# led30Sheet1.net
KiCad netlist of a schematic drawn in Altium Designer
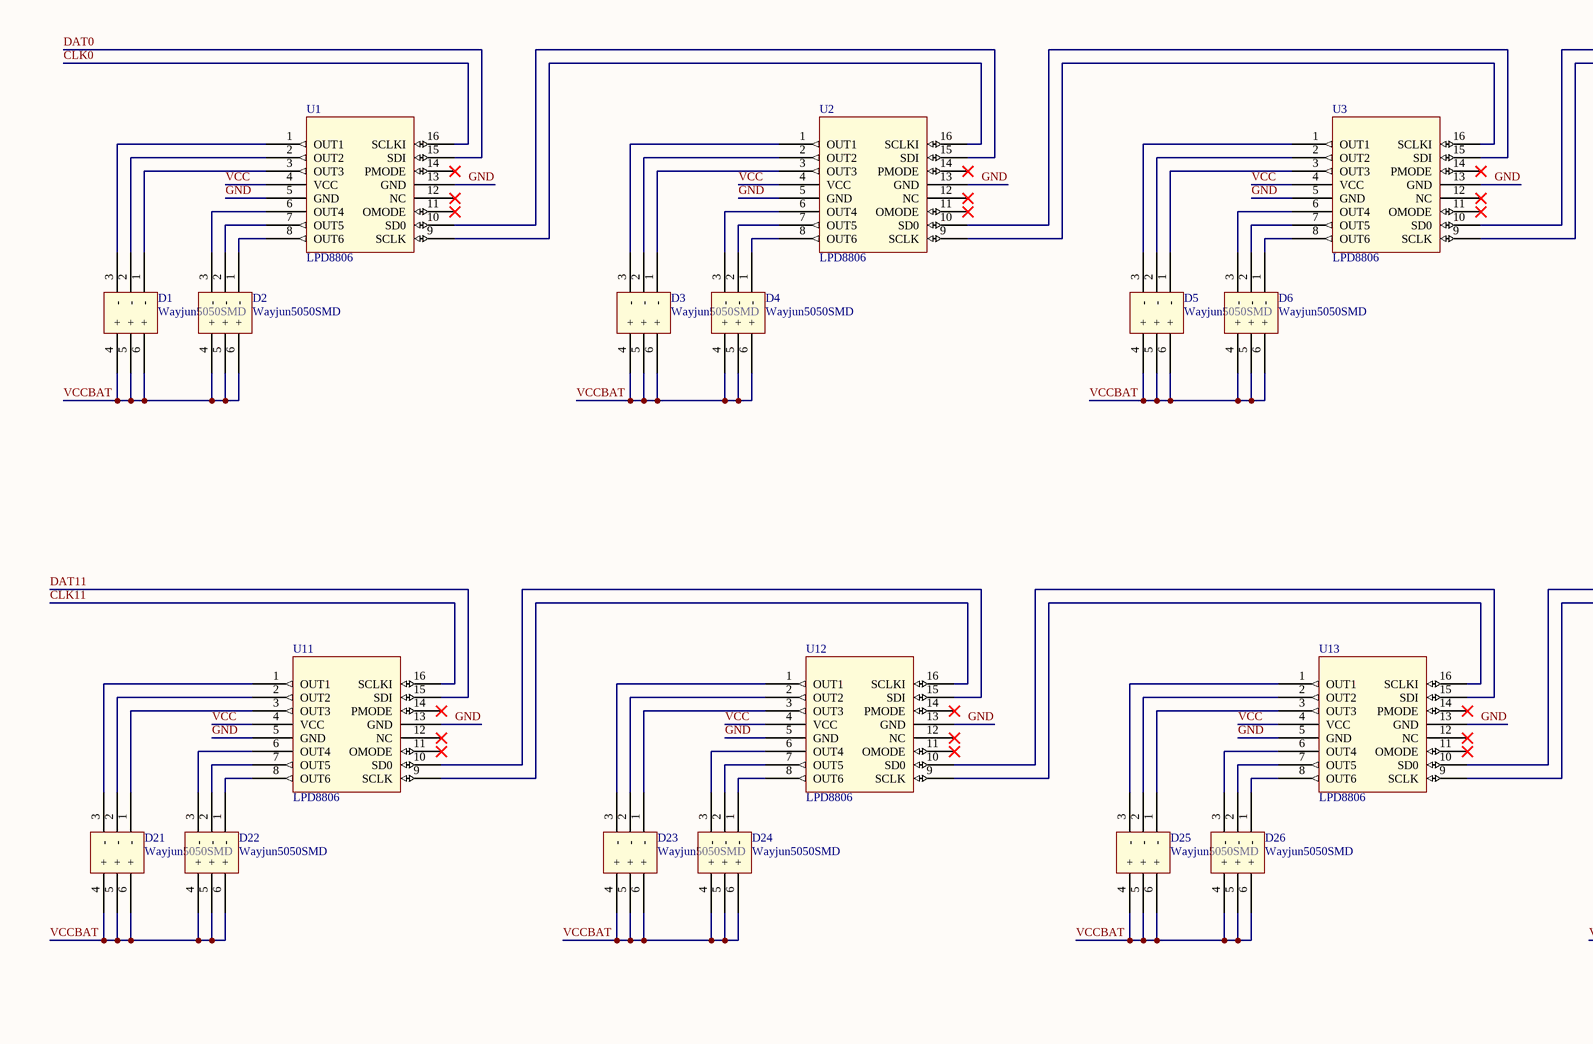
[diagram p0: led30Sheet1.SchDoc, top left]
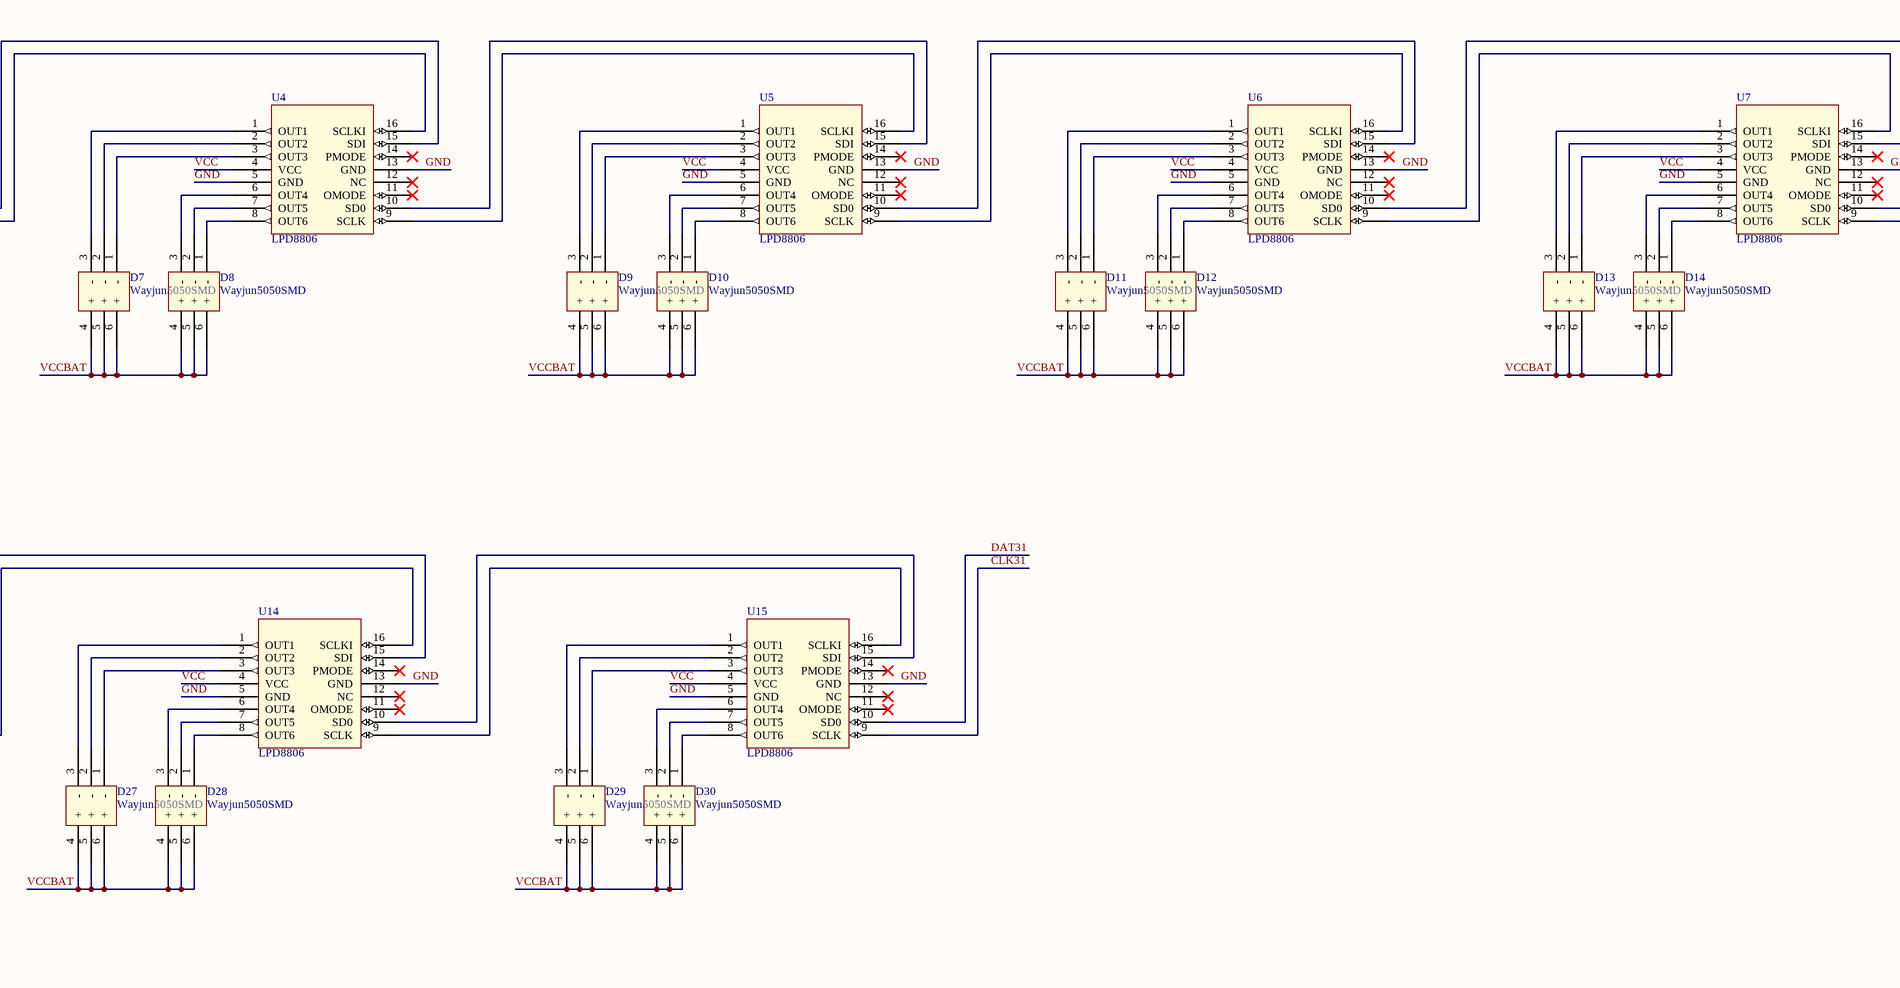
[diagram p1: led30Sheet1.SchDoc, top middle]
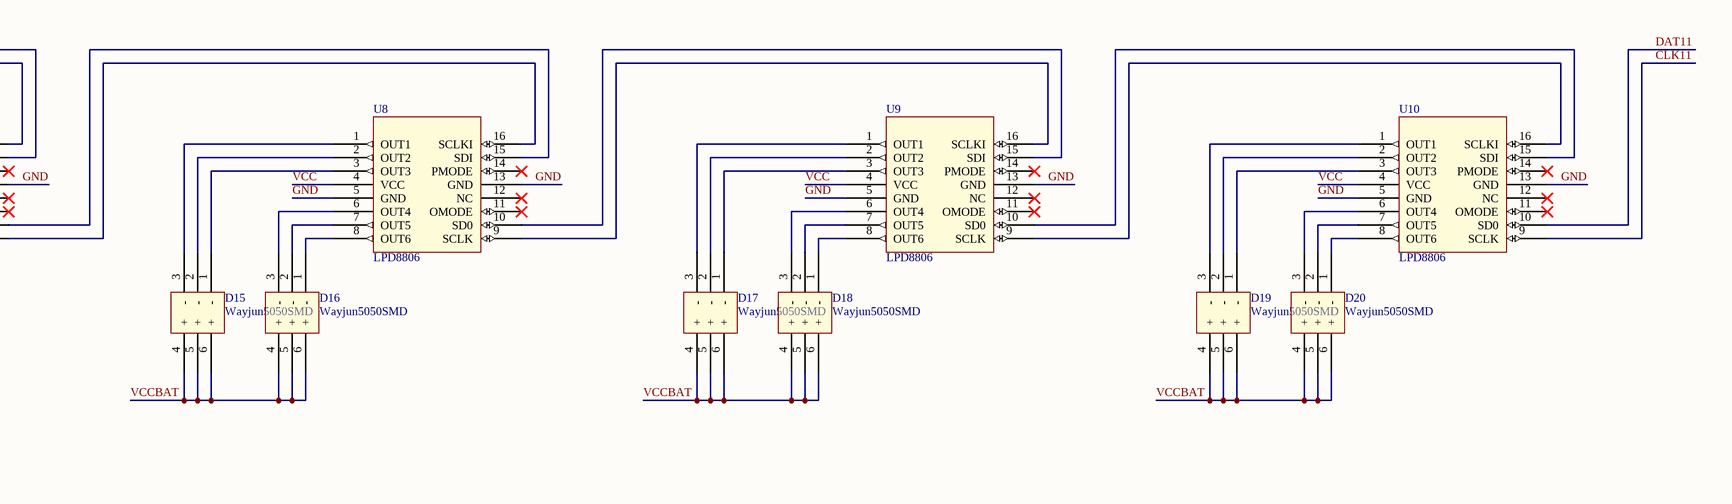
[diagram p2: led30Sheet1.SchDoc, top right]
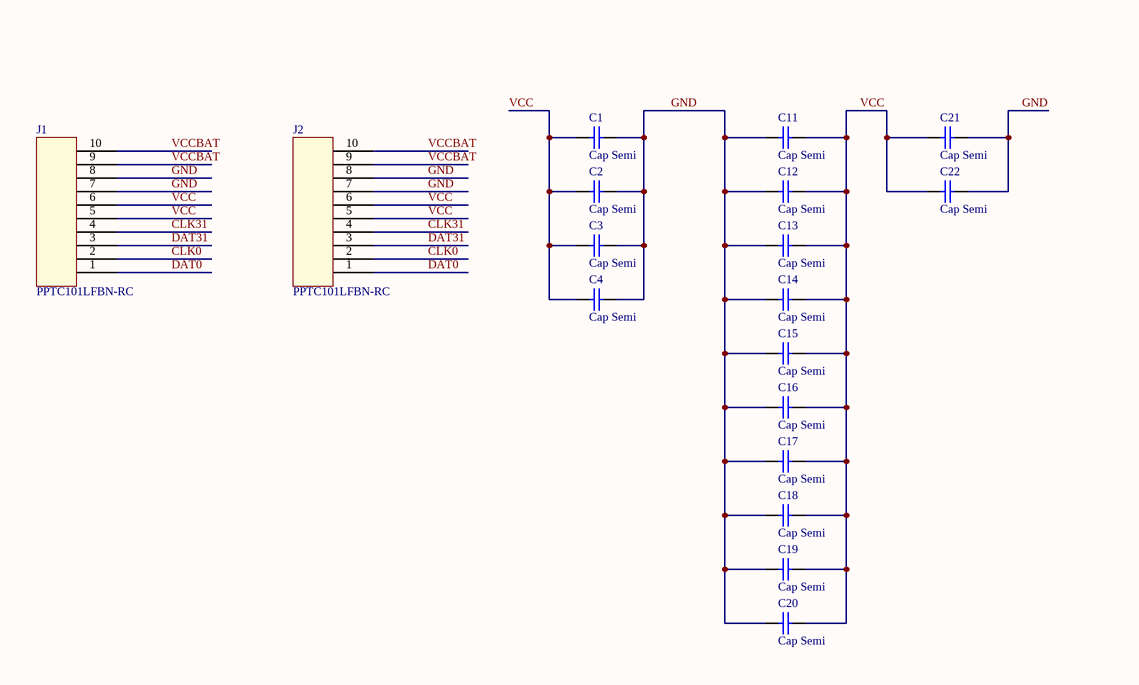
[diagram p3: led30Sheet1.SchDoc, bottom left]

(export (version "E")
  (design (tool "Eeschema 10.0.6"))
  (components
    (comp (ref "C1")
      (value "Cap Semi")
      (footprint "0402")
      (description "Capacitor (Semiconductor SIM Model)")
      (fields (field (name "PUBLISHER") "Altium Limited"))
      (libsource (lib "Miscellaneous Devices") (part "Cap Semi"))
    )
    (comp (ref "C2")
      (value "Cap Semi")
      (footprint "0402")
      (description "Capacitor (Semiconductor SIM Model)")
      (fields (field (name "PUBLISHER") "Altium Limited"))
      (libsource (lib "Miscellaneous Devices") (part "Cap Semi"))
    )
    (comp (ref "C3")
      (value "Cap Semi")
      (footprint "0402")
      (description "Capacitor (Semiconductor SIM Model)")
      (fields (field (name "PUBLISHER") "Altium Limited"))
      (libsource (lib "Miscellaneous Devices") (part "Cap Semi"))
    )
    (comp (ref "C4")
      (value "Cap Semi")
      (footprint "0402")
      (description "Capacitor (Semiconductor SIM Model)")
      (fields (field (name "PUBLISHER") "Altium Limited"))
      (libsource (lib "Miscellaneous Devices") (part "Cap Semi"))
    )
    (comp (ref "C11")
      (value "Cap Semi")
      (footprint "0402")
      (description "Capacitor (Semiconductor SIM Model)")
      (fields (field (name "PUBLISHER") "Altium Limited"))
      (libsource (lib "Miscellaneous Devices") (part "Cap Semi"))
    )
    (comp (ref "C12")
      (value "Cap Semi")
      (footprint "0402")
      (description "Capacitor (Semiconductor SIM Model)")
      (fields (field (name "PUBLISHER") "Altium Limited"))
      (libsource (lib "Miscellaneous Devices") (part "Cap Semi"))
    )
    (comp (ref "C13")
      (value "Cap Semi")
      (footprint "0402")
      (description "Capacitor (Semiconductor SIM Model)")
      (fields (field (name "PUBLISHER") "Altium Limited"))
      (libsource (lib "Miscellaneous Devices") (part "Cap Semi"))
    )
    (comp (ref "C14")
      (value "Cap Semi")
      (footprint "0402")
      (description "Capacitor (Semiconductor SIM Model)")
      (fields (field (name "PUBLISHER") "Altium Limited"))
      (libsource (lib "Miscellaneous Devices") (part "Cap Semi"))
    )
    (comp (ref "C15")
      (value "Cap Semi")
      (footprint "0402")
      (description "Capacitor (Semiconductor SIM Model)")
      (fields (field (name "PUBLISHER") "Altium Limited"))
      (libsource (lib "Miscellaneous Devices") (part "Cap Semi"))
    )
    (comp (ref "C16")
      (value "Cap Semi")
      (footprint "0402")
      (description "Capacitor (Semiconductor SIM Model)")
      (fields (field (name "PUBLISHER") "Altium Limited"))
      (libsource (lib "Miscellaneous Devices") (part "Cap Semi"))
    )
    (comp (ref "C17")
      (value "Cap Semi")
      (footprint "0402")
      (description "Capacitor (Semiconductor SIM Model)")
      (fields (field (name "PUBLISHER") "Altium Limited"))
      (libsource (lib "Miscellaneous Devices") (part "Cap Semi"))
    )
    (comp (ref "C18")
      (value "Cap Semi")
      (footprint "0402")
      (description "Capacitor (Semiconductor SIM Model)")
      (fields (field (name "PUBLISHER") "Altium Limited"))
      (libsource (lib "Miscellaneous Devices") (part "Cap Semi"))
    )
    (comp (ref "C19")
      (value "Cap Semi")
      (footprint "0402")
      (description "Capacitor (Semiconductor SIM Model)")
      (fields (field (name "PUBLISHER") "Altium Limited"))
      (libsource (lib "Miscellaneous Devices") (part "Cap Semi"))
    )
    (comp (ref "C20")
      (value "Cap Semi")
      (footprint "0402")
      (description "Capacitor (Semiconductor SIM Model)")
      (fields (field (name "PUBLISHER") "Altium Limited"))
      (libsource (lib "Miscellaneous Devices") (part "Cap Semi"))
    )
    (comp (ref "C21")
      (value "Cap Semi")
      (footprint "0402")
      (description "Capacitor (Semiconductor SIM Model)")
      (fields (field (name "PUBLISHER") "Altium Limited"))
      (libsource (lib "Miscellaneous Devices") (part "Cap Semi"))
    )
    (comp (ref "C22")
      (value "Cap Semi")
      (footprint "0402")
      (description "Capacitor (Semiconductor SIM Model)")
      (fields (field (name "PUBLISHER") "Altium Limited"))
      (libsource (lib "Miscellaneous Devices") (part "Cap Semi"))
    )
    (comp (ref "D1")
      (value "Wayjun5050SMD")
      (footprint "SON150P500X150_HS-7N")
      (libsource (lib "lightshow") (part "Wayjun5050SMD"))
    )
    (comp (ref "D2")
      (value "Wayjun5050SMD")
      (footprint "SON150P500X150_HS-7N")
      (libsource (lib "lightshow") (part "Wayjun5050SMD"))
    )
    (comp (ref "D3")
      (value "Wayjun5050SMD")
      (footprint "SON150P500X150_HS-7N")
      (libsource (lib "lightshow") (part "Wayjun5050SMD"))
    )
    (comp (ref "D4")
      (value "Wayjun5050SMD")
      (footprint "SON150P500X150_HS-7N")
      (libsource (lib "lightshow") (part "Wayjun5050SMD"))
    )
    (comp (ref "D5")
      (value "Wayjun5050SMD")
      (footprint "SON150P500X150_HS-7N")
      (libsource (lib "lightshow") (part "Wayjun5050SMD"))
    )
    (comp (ref "D6")
      (value "Wayjun5050SMD")
      (footprint "SON150P500X150_HS-7N")
      (libsource (lib "lightshow") (part "Wayjun5050SMD"))
    )
    (comp (ref "D7")
      (value "Wayjun5050SMD")
      (footprint "SON150P500X150_HS-7N")
      (libsource (lib "lightshow") (part "Wayjun5050SMD"))
    )
    (comp (ref "D8")
      (value "Wayjun5050SMD")
      (footprint "SON150P500X150_HS-7N")
      (libsource (lib "lightshow") (part "Wayjun5050SMD"))
    )
    (comp (ref "D9")
      (value "Wayjun5050SMD")
      (footprint "SON150P500X150_HS-7N")
      (libsource (lib "lightshow") (part "Wayjun5050SMD"))
    )
    (comp (ref "D10")
      (value "Wayjun5050SMD")
      (footprint "SON150P500X150_HS-7N")
      (libsource (lib "lightshow") (part "Wayjun5050SMD"))
    )
    (comp (ref "D11")
      (value "Wayjun5050SMD")
      (footprint "SON150P500X150_HS-7N")
      (libsource (lib "lightshow") (part "Wayjun5050SMD"))
    )
    (comp (ref "D12")
      (value "Wayjun5050SMD")
      (footprint "SON150P500X150_HS-7N")
      (libsource (lib "lightshow") (part "Wayjun5050SMD"))
    )
    (comp (ref "D13")
      (value "Wayjun5050SMD")
      (footprint "SON150P500X150_HS-7N")
      (libsource (lib "lightshow") (part "Wayjun5050SMD"))
    )
    (comp (ref "D14")
      (value "Wayjun5050SMD")
      (footprint "SON150P500X150_HS-7N")
      (libsource (lib "lightshow") (part "Wayjun5050SMD"))
    )
    (comp (ref "D15")
      (value "Wayjun5050SMD")
      (footprint "SON150P500X150_HS-7N")
      (libsource (lib "lightshow") (part "Wayjun5050SMD"))
    )
    (comp (ref "D16")
      (value "Wayjun5050SMD")
      (footprint "SON150P500X150_HS-7N")
      (libsource (lib "lightshow") (part "Wayjun5050SMD"))
    )
    (comp (ref "D17")
      (value "Wayjun5050SMD")
      (footprint "SON150P500X150_HS-7N")
      (libsource (lib "lightshow") (part "Wayjun5050SMD"))
    )
    (comp (ref "D18")
      (value "Wayjun5050SMD")
      (footprint "SON150P500X150_HS-7N")
      (libsource (lib "lightshow") (part "Wayjun5050SMD"))
    )
    (comp (ref "D19")
      (value "Wayjun5050SMD")
      (footprint "SON150P500X150_HS-7N")
      (libsource (lib "lightshow") (part "Wayjun5050SMD"))
    )
    (comp (ref "D20")
      (value "Wayjun5050SMD")
      (footprint "SON150P500X150_HS-7N")
      (libsource (lib "lightshow") (part "Wayjun5050SMD"))
    )
    (comp (ref "D21")
      (value "Wayjun5050SMD")
      (footprint "SON150P500X150_HS-7N")
      (libsource (lib "lightshow") (part "Wayjun5050SMD"))
    )
    (comp (ref "D22")
      (value "Wayjun5050SMD")
      (footprint "SON150P500X150_HS-7N")
      (libsource (lib "lightshow") (part "Wayjun5050SMD"))
    )
    (comp (ref "D23")
      (value "Wayjun5050SMD")
      (footprint "SON150P500X150_HS-7N")
      (libsource (lib "lightshow") (part "Wayjun5050SMD"))
    )
    (comp (ref "D24")
      (value "Wayjun5050SMD")
      (footprint "SON150P500X150_HS-7N")
      (libsource (lib "lightshow") (part "Wayjun5050SMD"))
    )
    (comp (ref "D25")
      (value "Wayjun5050SMD")
      (footprint "SON150P500X150_HS-7N")
      (libsource (lib "lightshow") (part "Wayjun5050SMD"))
    )
    (comp (ref "D26")
      (value "Wayjun5050SMD")
      (footprint "SON150P500X150_HS-7N")
      (libsource (lib "lightshow") (part "Wayjun5050SMD"))
    )
    (comp (ref "D27")
      (value "Wayjun5050SMD")
      (footprint "SON150P500X150_HS-7N")
      (libsource (lib "lightshow") (part "Wayjun5050SMD"))
    )
    (comp (ref "D28")
      (value "Wayjun5050SMD")
      (footprint "SON150P500X150_HS-7N")
      (libsource (lib "lightshow") (part "Wayjun5050SMD"))
    )
    (comp (ref "D29")
      (value "Wayjun5050SMD")
      (footprint "SON150P500X150_HS-7N")
      (libsource (lib "lightshow") (part "Wayjun5050SMD"))
    )
    (comp (ref "D30")
      (value "Wayjun5050SMD")
      (footprint "SON150P500X150_HS-7N")
      (libsource (lib "lightshow") (part "Wayjun5050SMD"))
    )
    (comp (ref "J1")
      (value "PPTC101LFBN-RC")
      (footprint "PPTC101LFBN-RC")
      (description "Sullins PPTC101LFBN-RC 10 Position Header Connector 0.100\" (2.54mm) Through Hole Tin")
      (libsource (lib "lightshow") (part "PPTC101LFBN-RC"))
    )
    (comp (ref "J2")
      (value "PPTC101LFBN-RC")
      (footprint "PPTC101LFBN-RC")
      (description "Sullins PPTC101LFBN-RC 10 Position Header Connector 0.100\" (2.54mm) Through Hole Tin")
      (libsource (lib "lightshow") (part "PPTC101LFBN-RC"))
    )
    (comp (ref "U1")
      (value "LPD8806")
      (footprint "SOP127P600-8N")
      (description "LPD8806 LED Driver")
      (libsource (lib "lightshow") (part "LPD8806"))
    )
    (comp (ref "U2")
      (value "LPD8806")
      (footprint "SOP127P600-8N")
      (description "LPD8806 LED Driver")
      (libsource (lib "lightshow") (part "LPD8806"))
    )
    (comp (ref "U3")
      (value "LPD8806")
      (footprint "SOP127P600-8N")
      (description "LPD8806 LED Driver")
      (libsource (lib "lightshow") (part "LPD8806"))
    )
    (comp (ref "U4")
      (value "LPD8806")
      (footprint "SOP127P600-8N")
      (description "LPD8806 LED Driver")
      (libsource (lib "lightshow") (part "LPD8806"))
    )
    (comp (ref "U5")
      (value "LPD8806")
      (footprint "SOP127P600-8N")
      (description "LPD8806 LED Driver")
      (libsource (lib "lightshow") (part "LPD8806"))
    )
    (comp (ref "U6")
      (value "LPD8806")
      (footprint "SOP127P600-8N")
      (description "LPD8806 LED Driver")
      (libsource (lib "lightshow") (part "LPD8806"))
    )
    (comp (ref "U7")
      (value "LPD8806")
      (footprint "SOP127P600-8N")
      (description "LPD8806 LED Driver")
      (libsource (lib "lightshow") (part "LPD8806"))
    )
    (comp (ref "U8")
      (value "LPD8806")
      (footprint "SOP127P600-8N")
      (description "LPD8806 LED Driver")
      (libsource (lib "lightshow") (part "LPD8806"))
    )
    (comp (ref "U9")
      (value "LPD8806")
      (footprint "SOP127P600-8N")
      (description "LPD8806 LED Driver")
      (libsource (lib "lightshow") (part "LPD8806"))
    )
    (comp (ref "U10")
      (value "LPD8806")
      (footprint "SOP127P600-8N")
      (description "LPD8806 LED Driver")
      (libsource (lib "lightshow") (part "LPD8806"))
    )
    (comp (ref "U11")
      (value "LPD8806")
      (footprint "SOP127P600-8N")
      (description "LPD8806 LED Driver")
      (libsource (lib "lightshow") (part "LPD8806"))
    )
    (comp (ref "U12")
      (value "LPD8806")
      (footprint "SOP127P600-8N")
      (description "LPD8806 LED Driver")
      (libsource (lib "lightshow") (part "LPD8806"))
    )
    (comp (ref "U13")
      (value "LPD8806")
      (footprint "SOP127P600-8N")
      (description "LPD8806 LED Driver")
      (libsource (lib "lightshow") (part "LPD8806"))
    )
    (comp (ref "U14")
      (value "LPD8806")
      (footprint "SOP127P600-8N")
      (description "LPD8806 LED Driver")
      (libsource (lib "lightshow") (part "LPD8806"))
    )
    (comp (ref "U15")
      (value "LPD8806")
      (footprint "SOP127P600-8N")
      (description "LPD8806 LED Driver")
      (libsource (lib "lightshow") (part "LPD8806"))
    )
  )
  (nets
    (net (code "1") (name "/CLK0") (class "Default")
      (node (ref "J1") (pin "2") (pintype "passive"))
      (node (ref "J2") (pin "2") (pintype "passive"))
      (node (ref "U1") (pin "16") (pinfunction "SCLKI_16") (pintype "bidirectional"))
    )
    (net (code "2") (name "/CLK11") (class "Default")
      (node (ref "U10") (pin "9") (pinfunction "SCLK_9") (pintype "bidirectional"))
      (node (ref "U11") (pin "16") (pinfunction "SCLKI_16") (pintype "bidirectional"))
    )
    (net (code "3") (name "/CLK31") (class "Default")
      (node (ref "J1") (pin "4") (pintype "passive"))
      (node (ref "J2") (pin "4") (pintype "passive"))
      (node (ref "U15") (pin "9") (pinfunction "SCLK_9") (pintype "bidirectional"))
    )
    (net (code "4") (name "/DAT0") (class "Default")
      (node (ref "J1") (pin "1") (pintype "passive"))
      (node (ref "J2") (pin "1") (pintype "passive"))
      (node (ref "U1") (pin "15") (pinfunction "SDI_15") (pintype "bidirectional"))
    )
    (net (code "5") (name "/DAT11") (class "Default")
      (node (ref "U10") (pin "10") (pinfunction "SD0_10") (pintype "bidirectional"))
      (node (ref "U11") (pin "15") (pinfunction "SDI_15") (pintype "bidirectional"))
    )
    (net (code "6") (name "/DAT31") (class "Default")
      (node (ref "J1") (pin "3") (pintype "passive"))
      (node (ref "J2") (pin "3") (pintype "passive"))
      (node (ref "U15") (pin "10") (pinfunction "SD0_10") (pintype "bidirectional"))
    )
    (net (code "7") (name "/GND") (class "Default")
      (node (ref "C1") (pin "2") (pinfunction "2_2") (pintype "passive"))
      (node (ref "C11") (pin "1") (pinfunction "1_1") (pintype "passive"))
      (node (ref "C12") (pin "1") (pinfunction "1_1") (pintype "passive"))
      (node (ref "C13") (pin "1") (pinfunction "1_1") (pintype "passive"))
      (node (ref "C14") (pin "1") (pinfunction "1_1") (pintype "passive"))
      (node (ref "C15") (pin "1") (pinfunction "1_1") (pintype "passive"))
      (node (ref "C16") (pin "1") (pinfunction "1_1") (pintype "passive"))
      (node (ref "C17") (pin "1") (pinfunction "1_1") (pintype "passive"))
      (node (ref "C18") (pin "1") (pinfunction "1_1") (pintype "passive"))
      (node (ref "C19") (pin "1") (pinfunction "1_1") (pintype "passive"))
      (node (ref "C2") (pin "2") (pinfunction "2_2") (pintype "passive"))
      (node (ref "C20") (pin "1") (pinfunction "1_1") (pintype "passive"))
      (node (ref "C21") (pin "2") (pinfunction "2_2") (pintype "passive"))
      (node (ref "C22") (pin "2") (pinfunction "2_2") (pintype "passive"))
      (node (ref "C3") (pin "2") (pinfunction "2_2") (pintype "passive"))
      (node (ref "C4") (pin "2") (pinfunction "2_2") (pintype "passive"))
      (node (ref "J1") (pin "7") (pintype "passive"))
      (node (ref "J1") (pin "8") (pintype "passive"))
      (node (ref "J2") (pin "7") (pintype "passive"))
      (node (ref "J2") (pin "8") (pintype "passive"))
      (node (ref "U1") (pin "13") (pinfunction "GND_13") (pintype "power_in"))
      (node (ref "U1") (pin "5") (pinfunction "GND_5") (pintype "power_in"))
      (node (ref "U10") (pin "13") (pinfunction "GND_13") (pintype "power_in"))
      (node (ref "U10") (pin "5") (pinfunction "GND_5") (pintype "power_in"))
      (node (ref "U11") (pin "13") (pinfunction "GND_13") (pintype "power_in"))
      (node (ref "U11") (pin "5") (pinfunction "GND_5") (pintype "power_in"))
      (node (ref "U12") (pin "13") (pinfunction "GND_13") (pintype "power_in"))
      (node (ref "U12") (pin "5") (pinfunction "GND_5") (pintype "power_in"))
      (node (ref "U13") (pin "13") (pinfunction "GND_13") (pintype "power_in"))
      (node (ref "U13") (pin "5") (pinfunction "GND_5") (pintype "power_in"))
      (node (ref "U14") (pin "13") (pinfunction "GND_13") (pintype "power_in"))
      (node (ref "U14") (pin "5") (pinfunction "GND_5") (pintype "power_in"))
      (node (ref "U15") (pin "13") (pinfunction "GND_13") (pintype "power_in"))
      (node (ref "U15") (pin "5") (pinfunction "GND_5") (pintype "power_in"))
      (node (ref "U2") (pin "13") (pinfunction "GND_13") (pintype "power_in"))
      (node (ref "U2") (pin "5") (pinfunction "GND_5") (pintype "power_in"))
      (node (ref "U3") (pin "13") (pinfunction "GND_13") (pintype "power_in"))
      (node (ref "U3") (pin "5") (pinfunction "GND_5") (pintype "power_in"))
      (node (ref "U4") (pin "13") (pinfunction "GND_13") (pintype "power_in"))
      (node (ref "U4") (pin "5") (pinfunction "GND_5") (pintype "power_in"))
      (node (ref "U5") (pin "13") (pinfunction "GND_13") (pintype "power_in"))
      (node (ref "U5") (pin "5") (pinfunction "GND_5") (pintype "power_in"))
      (node (ref "U6") (pin "13") (pinfunction "GND_13") (pintype "power_in"))
      (node (ref "U6") (pin "5") (pinfunction "GND_5") (pintype "power_in"))
      (node (ref "U7") (pin "13") (pinfunction "GND_13") (pintype "power_in"))
      (node (ref "U7") (pin "5") (pinfunction "GND_5") (pintype "power_in"))
      (node (ref "U8") (pin "13") (pinfunction "GND_13") (pintype "power_in"))
      (node (ref "U8") (pin "5") (pinfunction "GND_5") (pintype "power_in"))
      (node (ref "U9") (pin "13") (pinfunction "GND_13") (pintype "power_in"))
      (node (ref "U9") (pin "5") (pinfunction "GND_5") (pintype "power_in"))
    )
    (net (code "8") (name "/VCC") (class "Default")
      (node (ref "C1") (pin "1") (pinfunction "1_1") (pintype "passive"))
      (node (ref "C11") (pin "2") (pinfunction "2_2") (pintype "passive"))
      (node (ref "C12") (pin "2") (pinfunction "2_2") (pintype "passive"))
      (node (ref "C13") (pin "2") (pinfunction "2_2") (pintype "passive"))
      (node (ref "C14") (pin "2") (pinfunction "2_2") (pintype "passive"))
      (node (ref "C15") (pin "2") (pinfunction "2_2") (pintype "passive"))
      (node (ref "C16") (pin "2") (pinfunction "2_2") (pintype "passive"))
      (node (ref "C17") (pin "2") (pinfunction "2_2") (pintype "passive"))
      (node (ref "C18") (pin "2") (pinfunction "2_2") (pintype "passive"))
      (node (ref "C19") (pin "2") (pinfunction "2_2") (pintype "passive"))
      (node (ref "C2") (pin "1") (pinfunction "1_1") (pintype "passive"))
      (node (ref "C20") (pin "2") (pinfunction "2_2") (pintype "passive"))
      (node (ref "C21") (pin "1") (pinfunction "1_1") (pintype "passive"))
      (node (ref "C22") (pin "1") (pinfunction "1_1") (pintype "passive"))
      (node (ref "C3") (pin "1") (pinfunction "1_1") (pintype "passive"))
      (node (ref "C4") (pin "1") (pinfunction "1_1") (pintype "passive"))
      (node (ref "J1") (pin "5") (pintype "passive"))
      (node (ref "J1") (pin "6") (pintype "passive"))
      (node (ref "J2") (pin "5") (pintype "passive"))
      (node (ref "J2") (pin "6") (pintype "passive"))
      (node (ref "U1") (pin "4") (pinfunction "VCC_4") (pintype "power_in"))
      (node (ref "U10") (pin "4") (pinfunction "VCC_4") (pintype "power_in"))
      (node (ref "U11") (pin "4") (pinfunction "VCC_4") (pintype "power_in"))
      (node (ref "U12") (pin "4") (pinfunction "VCC_4") (pintype "power_in"))
      (node (ref "U13") (pin "4") (pinfunction "VCC_4") (pintype "power_in"))
      (node (ref "U14") (pin "4") (pinfunction "VCC_4") (pintype "power_in"))
      (node (ref "U15") (pin "4") (pinfunction "VCC_4") (pintype "power_in"))
      (node (ref "U2") (pin "4") (pinfunction "VCC_4") (pintype "power_in"))
      (node (ref "U3") (pin "4") (pinfunction "VCC_4") (pintype "power_in"))
      (node (ref "U4") (pin "4") (pinfunction "VCC_4") (pintype "power_in"))
      (node (ref "U5") (pin "4") (pinfunction "VCC_4") (pintype "power_in"))
      (node (ref "U6") (pin "4") (pinfunction "VCC_4") (pintype "power_in"))
      (node (ref "U7") (pin "4") (pinfunction "VCC_4") (pintype "power_in"))
      (node (ref "U8") (pin "4") (pinfunction "VCC_4") (pintype "power_in"))
      (node (ref "U9") (pin "4") (pinfunction "VCC_4") (pintype "power_in"))
    )
    (net (code "9") (name "/VCCBAT") (class "Default")
      (node (ref "D1") (pin "4") (pinfunction "+_4") (pintype "passive"))
      (node (ref "D1") (pin "5") (pinfunction "+_5") (pintype "passive"))
      (node (ref "D1") (pin "6") (pinfunction "+_6") (pintype "passive"))
      (node (ref "D10") (pin "4") (pinfunction "+_4") (pintype "passive"))
      (node (ref "D10") (pin "5") (pinfunction "+_5") (pintype "passive"))
      (node (ref "D10") (pin "6") (pinfunction "+_6") (pintype "passive"))
      (node (ref "D11") (pin "4") (pinfunction "+_4") (pintype "passive"))
      (node (ref "D11") (pin "5") (pinfunction "+_5") (pintype "passive"))
      (node (ref "D11") (pin "6") (pinfunction "+_6") (pintype "passive"))
      (node (ref "D12") (pin "4") (pinfunction "+_4") (pintype "passive"))
      (node (ref "D12") (pin "5") (pinfunction "+_5") (pintype "passive"))
      (node (ref "D12") (pin "6") (pinfunction "+_6") (pintype "passive"))
      (node (ref "D13") (pin "4") (pinfunction "+_4") (pintype "passive"))
      (node (ref "D13") (pin "5") (pinfunction "+_5") (pintype "passive"))
      (node (ref "D13") (pin "6") (pinfunction "+_6") (pintype "passive"))
      (node (ref "D14") (pin "4") (pinfunction "+_4") (pintype "passive"))
      (node (ref "D14") (pin "5") (pinfunction "+_5") (pintype "passive"))
      (node (ref "D14") (pin "6") (pinfunction "+_6") (pintype "passive"))
      (node (ref "D15") (pin "4") (pinfunction "+_4") (pintype "passive"))
      (node (ref "D15") (pin "5") (pinfunction "+_5") (pintype "passive"))
      (node (ref "D15") (pin "6") (pinfunction "+_6") (pintype "passive"))
      (node (ref "D16") (pin "4") (pinfunction "+_4") (pintype "passive"))
      (node (ref "D16") (pin "5") (pinfunction "+_5") (pintype "passive"))
      (node (ref "D16") (pin "6") (pinfunction "+_6") (pintype "passive"))
      (node (ref "D17") (pin "4") (pinfunction "+_4") (pintype "passive"))
      (node (ref "D17") (pin "5") (pinfunction "+_5") (pintype "passive"))
      (node (ref "D17") (pin "6") (pinfunction "+_6") (pintype "passive"))
      (node (ref "D18") (pin "4") (pinfunction "+_4") (pintype "passive"))
      (node (ref "D18") (pin "5") (pinfunction "+_5") (pintype "passive"))
      (node (ref "D18") (pin "6") (pinfunction "+_6") (pintype "passive"))
      (node (ref "D19") (pin "4") (pinfunction "+_4") (pintype "passive"))
      (node (ref "D19") (pin "5") (pinfunction "+_5") (pintype "passive"))
      (node (ref "D19") (pin "6") (pinfunction "+_6") (pintype "passive"))
      (node (ref "D2") (pin "4") (pinfunction "+_4") (pintype "passive"))
      (node (ref "D2") (pin "5") (pinfunction "+_5") (pintype "passive"))
      (node (ref "D2") (pin "6") (pinfunction "+_6") (pintype "passive"))
      (node (ref "D20") (pin "4") (pinfunction "+_4") (pintype "passive"))
      (node (ref "D20") (pin "5") (pinfunction "+_5") (pintype "passive"))
      (node (ref "D20") (pin "6") (pinfunction "+_6") (pintype "passive"))
      (node (ref "D21") (pin "4") (pinfunction "+_4") (pintype "passive"))
      (node (ref "D21") (pin "5") (pinfunction "+_5") (pintype "passive"))
      (node (ref "D21") (pin "6") (pinfunction "+_6") (pintype "passive"))
      (node (ref "D22") (pin "4") (pinfunction "+_4") (pintype "passive"))
      (node (ref "D22") (pin "5") (pinfunction "+_5") (pintype "passive"))
      (node (ref "D22") (pin "6") (pinfunction "+_6") (pintype "passive"))
      (node (ref "D23") (pin "4") (pinfunction "+_4") (pintype "passive"))
      (node (ref "D23") (pin "5") (pinfunction "+_5") (pintype "passive"))
      (node (ref "D23") (pin "6") (pinfunction "+_6") (pintype "passive"))
      (node (ref "D24") (pin "4") (pinfunction "+_4") (pintype "passive"))
      (node (ref "D24") (pin "5") (pinfunction "+_5") (pintype "passive"))
      (node (ref "D24") (pin "6") (pinfunction "+_6") (pintype "passive"))
      (node (ref "D25") (pin "4") (pinfunction "+_4") (pintype "passive"))
      (node (ref "D25") (pin "5") (pinfunction "+_5") (pintype "passive"))
      (node (ref "D25") (pin "6") (pinfunction "+_6") (pintype "passive"))
      (node (ref "D26") (pin "4") (pinfunction "+_4") (pintype "passive"))
      (node (ref "D26") (pin "5") (pinfunction "+_5") (pintype "passive"))
      (node (ref "D26") (pin "6") (pinfunction "+_6") (pintype "passive"))
      (node (ref "D27") (pin "4") (pinfunction "+_4") (pintype "passive"))
      (node (ref "D27") (pin "5") (pinfunction "+_5") (pintype "passive"))
      (node (ref "D27") (pin "6") (pinfunction "+_6") (pintype "passive"))
      (node (ref "D28") (pin "4") (pinfunction "+_4") (pintype "passive"))
      (node (ref "D28") (pin "5") (pinfunction "+_5") (pintype "passive"))
      (node (ref "D28") (pin "6") (pinfunction "+_6") (pintype "passive"))
      (node (ref "D29") (pin "4") (pinfunction "+_4") (pintype "passive"))
      (node (ref "D29") (pin "5") (pinfunction "+_5") (pintype "passive"))
      (node (ref "D29") (pin "6") (pinfunction "+_6") (pintype "passive"))
      (node (ref "D3") (pin "4") (pinfunction "+_4") (pintype "passive"))
      (node (ref "D3") (pin "5") (pinfunction "+_5") (pintype "passive"))
      (node (ref "D3") (pin "6") (pinfunction "+_6") (pintype "passive"))
      (node (ref "D30") (pin "4") (pinfunction "+_4") (pintype "passive"))
      (node (ref "D30") (pin "5") (pinfunction "+_5") (pintype "passive"))
      (node (ref "D30") (pin "6") (pinfunction "+_6") (pintype "passive"))
      (node (ref "D4") (pin "4") (pinfunction "+_4") (pintype "passive"))
      (node (ref "D4") (pin "5") (pinfunction "+_5") (pintype "passive"))
      (node (ref "D4") (pin "6") (pinfunction "+_6") (pintype "passive"))
      (node (ref "D5") (pin "4") (pinfunction "+_4") (pintype "passive"))
      (node (ref "D5") (pin "5") (pinfunction "+_5") (pintype "passive"))
      (node (ref "D5") (pin "6") (pinfunction "+_6") (pintype "passive"))
      (node (ref "D6") (pin "4") (pinfunction "+_4") (pintype "passive"))
      (node (ref "D6") (pin "5") (pinfunction "+_5") (pintype "passive"))
      (node (ref "D6") (pin "6") (pinfunction "+_6") (pintype "passive"))
      (node (ref "D7") (pin "4") (pinfunction "+_4") (pintype "passive"))
      (node (ref "D7") (pin "5") (pinfunction "+_5") (pintype "passive"))
      (node (ref "D7") (pin "6") (pinfunction "+_6") (pintype "passive"))
      (node (ref "D8") (pin "4") (pinfunction "+_4") (pintype "passive"))
      (node (ref "D8") (pin "5") (pinfunction "+_5") (pintype "passive"))
      (node (ref "D8") (pin "6") (pinfunction "+_6") (pintype "passive"))
      (node (ref "D9") (pin "4") (pinfunction "+_4") (pintype "passive"))
      (node (ref "D9") (pin "5") (pinfunction "+_5") (pintype "passive"))
      (node (ref "D9") (pin "6") (pinfunction "+_6") (pintype "passive"))
      (node (ref "J1") (pin "10") (pintype "passive"))
      (node (ref "J1") (pin "9") (pintype "passive"))
      (node (ref "J2") (pin "10") (pintype "passive"))
      (node (ref "J2") (pin "9") (pintype "passive"))
    )
    (net (code "10") (name "Net-(U1-OUT1)") (class "Default")
      (node (ref "D1") (pin "3") (pinfunction "-_3") (pintype "passive"))
      (node (ref "U1") (pin "1") (pinfunction "OUT1_1") (pintype "output"))
    )
    (net (code "11") (name "Net-(U1-OUT2)") (class "Default")
      (node (ref "D1") (pin "2") (pinfunction "-_2") (pintype "passive"))
      (node (ref "U1") (pin "2") (pinfunction "OUT2_2") (pintype "output"))
    )
    (net (code "12") (name "Net-(U1-OUT3)") (class "Default")
      (node (ref "D1") (pin "1") (pinfunction "-_1") (pintype "passive"))
      (node (ref "U1") (pin "3") (pinfunction "OUT3_3") (pintype "output"))
    )
    (net (code "13") (name "Net-(U1-OUT4)") (class "Default")
      (node (ref "D2") (pin "3") (pinfunction "-_3") (pintype "passive"))
      (node (ref "U1") (pin "6") (pinfunction "OUT4_6") (pintype "power_in"))
    )
    (net (code "14") (name "Net-(U1-OUT5)") (class "Default")
      (node (ref "D2") (pin "2") (pinfunction "-_2") (pintype "passive"))
      (node (ref "U1") (pin "7") (pinfunction "OUT5_7") (pintype "output"))
    )
    (net (code "15") (name "Net-(U1-OUT6)") (class "Default")
      (node (ref "D2") (pin "1") (pinfunction "-_1") (pintype "passive"))
      (node (ref "U1") (pin "8") (pinfunction "OUT6_8") (pintype "output"))
    )
    (net (code "16") (name "Net-(U1-SCLK)") (class "Default")
      (node (ref "U1") (pin "9") (pinfunction "SCLK_9") (pintype "bidirectional"))
      (node (ref "U2") (pin "16") (pinfunction "SCLKI_16") (pintype "bidirectional"))
    )
    (net (code "17") (name "Net-(U1-SD0)") (class "Default")
      (node (ref "U1") (pin "10") (pinfunction "SD0_10") (pintype "bidirectional"))
      (node (ref "U2") (pin "15") (pinfunction "SDI_15") (pintype "bidirectional"))
    )
    (net (code "18") (name "Net-(U2-OUT1)") (class "Default")
      (node (ref "D3") (pin "3") (pinfunction "-_3") (pintype "passive"))
      (node (ref "U2") (pin "1") (pinfunction "OUT1_1") (pintype "output"))
    )
    (net (code "19") (name "Net-(U2-OUT2)") (class "Default")
      (node (ref "D3") (pin "2") (pinfunction "-_2") (pintype "passive"))
      (node (ref "U2") (pin "2") (pinfunction "OUT2_2") (pintype "output"))
    )
    (net (code "20") (name "Net-(U2-OUT3)") (class "Default")
      (node (ref "D3") (pin "1") (pinfunction "-_1") (pintype "passive"))
      (node (ref "U2") (pin "3") (pinfunction "OUT3_3") (pintype "output"))
    )
    (net (code "21") (name "Net-(U2-OUT4)") (class "Default")
      (node (ref "D4") (pin "3") (pinfunction "-_3") (pintype "passive"))
      (node (ref "U2") (pin "6") (pinfunction "OUT4_6") (pintype "power_in"))
    )
    (net (code "22") (name "Net-(U2-OUT5)") (class "Default")
      (node (ref "D4") (pin "2") (pinfunction "-_2") (pintype "passive"))
      (node (ref "U2") (pin "7") (pinfunction "OUT5_7") (pintype "output"))
    )
    (net (code "23") (name "Net-(U2-OUT6)") (class "Default")
      (node (ref "D4") (pin "1") (pinfunction "-_1") (pintype "passive"))
      (node (ref "U2") (pin "8") (pinfunction "OUT6_8") (pintype "output"))
    )
    (net (code "24") (name "Net-(U2-SCLK)") (class "Default")
      (node (ref "U2") (pin "9") (pinfunction "SCLK_9") (pintype "bidirectional"))
      (node (ref "U3") (pin "16") (pinfunction "SCLKI_16") (pintype "bidirectional"))
    )
    (net (code "25") (name "Net-(U2-SD0)") (class "Default")
      (node (ref "U2") (pin "10") (pinfunction "SD0_10") (pintype "bidirectional"))
      (node (ref "U3") (pin "15") (pinfunction "SDI_15") (pintype "bidirectional"))
    )
    (net (code "26") (name "Net-(U3-OUT1)") (class "Default")
      (node (ref "D5") (pin "3") (pinfunction "-_3") (pintype "passive"))
      (node (ref "U3") (pin "1") (pinfunction "OUT1_1") (pintype "output"))
    )
    (net (code "27") (name "Net-(U3-OUT2)") (class "Default")
      (node (ref "D5") (pin "2") (pinfunction "-_2") (pintype "passive"))
      (node (ref "U3") (pin "2") (pinfunction "OUT2_2") (pintype "output"))
    )
    (net (code "28") (name "Net-(U3-OUT3)") (class "Default")
      (node (ref "D5") (pin "1") (pinfunction "-_1") (pintype "passive"))
      (node (ref "U3") (pin "3") (pinfunction "OUT3_3") (pintype "output"))
    )
    (net (code "29") (name "Net-(U3-OUT4)") (class "Default")
      (node (ref "D6") (pin "3") (pinfunction "-_3") (pintype "passive"))
      (node (ref "U3") (pin "6") (pinfunction "OUT4_6") (pintype "power_in"))
    )
    (net (code "30") (name "Net-(U3-OUT5)") (class "Default")
      (node (ref "D6") (pin "2") (pinfunction "-_2") (pintype "passive"))
      (node (ref "U3") (pin "7") (pinfunction "OUT5_7") (pintype "output"))
    )
    (net (code "31") (name "Net-(U3-OUT6)") (class "Default")
      (node (ref "D6") (pin "1") (pinfunction "-_1") (pintype "passive"))
      (node (ref "U3") (pin "8") (pinfunction "OUT6_8") (pintype "output"))
    )
    (net (code "32") (name "Net-(U3-SCLK)") (class "Default")
      (node (ref "U3") (pin "9") (pinfunction "SCLK_9") (pintype "bidirectional"))
      (node (ref "U4") (pin "16") (pinfunction "SCLKI_16") (pintype "bidirectional"))
    )
    (net (code "33") (name "Net-(U3-SD0)") (class "Default")
      (node (ref "U3") (pin "10") (pinfunction "SD0_10") (pintype "bidirectional"))
      (node (ref "U4") (pin "15") (pinfunction "SDI_15") (pintype "bidirectional"))
    )
    (net (code "34") (name "Net-(U4-OUT1)") (class "Default")
      (node (ref "D7") (pin "3") (pinfunction "-_3") (pintype "passive"))
      (node (ref "U4") (pin "1") (pinfunction "OUT1_1") (pintype "output"))
    )
    (net (code "35") (name "Net-(U4-OUT2)") (class "Default")
      (node (ref "D7") (pin "2") (pinfunction "-_2") (pintype "passive"))
      (node (ref "U4") (pin "2") (pinfunction "OUT2_2") (pintype "output"))
    )
    (net (code "36") (name "Net-(U4-OUT3)") (class "Default")
      (node (ref "D7") (pin "1") (pinfunction "-_1") (pintype "passive"))
      (node (ref "U4") (pin "3") (pinfunction "OUT3_3") (pintype "output"))
    )
    (net (code "37") (name "Net-(U4-OUT4)") (class "Default")
      (node (ref "D8") (pin "3") (pinfunction "-_3") (pintype "passive"))
      (node (ref "U4") (pin "6") (pinfunction "OUT4_6") (pintype "power_in"))
    )
    (net (code "38") (name "Net-(U4-OUT5)") (class "Default")
      (node (ref "D8") (pin "2") (pinfunction "-_2") (pintype "passive"))
      (node (ref "U4") (pin "7") (pinfunction "OUT5_7") (pintype "output"))
    )
    (net (code "39") (name "Net-(U4-OUT6)") (class "Default")
      (node (ref "D8") (pin "1") (pinfunction "-_1") (pintype "passive"))
      (node (ref "U4") (pin "8") (pinfunction "OUT6_8") (pintype "output"))
    )
    (net (code "40") (name "Net-(U4-SCLK)") (class "Default")
      (node (ref "U4") (pin "9") (pinfunction "SCLK_9") (pintype "bidirectional"))
      (node (ref "U5") (pin "16") (pinfunction "SCLKI_16") (pintype "bidirectional"))
    )
    (net (code "41") (name "Net-(U4-SD0)") (class "Default")
      (node (ref "U4") (pin "10") (pinfunction "SD0_10") (pintype "bidirectional"))
      (node (ref "U5") (pin "15") (pinfunction "SDI_15") (pintype "bidirectional"))
    )
    (net (code "42") (name "Net-(U5-OUT1)") (class "Default")
      (node (ref "D9") (pin "3") (pinfunction "-_3") (pintype "passive"))
      (node (ref "U5") (pin "1") (pinfunction "OUT1_1") (pintype "output"))
    )
    (net (code "43") (name "Net-(U5-OUT2)") (class "Default")
      (node (ref "D9") (pin "2") (pinfunction "-_2") (pintype "passive"))
      (node (ref "U5") (pin "2") (pinfunction "OUT2_2") (pintype "output"))
    )
    (net (code "44") (name "Net-(U5-OUT3)") (class "Default")
      (node (ref "D9") (pin "1") (pinfunction "-_1") (pintype "passive"))
      (node (ref "U5") (pin "3") (pinfunction "OUT3_3") (pintype "output"))
    )
    (net (code "45") (name "Net-(U5-OUT4)") (class "Default")
      (node (ref "D10") (pin "3") (pinfunction "-_3") (pintype "passive"))
      (node (ref "U5") (pin "6") (pinfunction "OUT4_6") (pintype "power_in"))
    )
    (net (code "46") (name "Net-(U5-OUT5)") (class "Default")
      (node (ref "D10") (pin "2") (pinfunction "-_2") (pintype "passive"))
      (node (ref "U5") (pin "7") (pinfunction "OUT5_7") (pintype "output"))
    )
    (net (code "47") (name "Net-(U5-OUT6)") (class "Default")
      (node (ref "D10") (pin "1") (pinfunction "-_1") (pintype "passive"))
      (node (ref "U5") (pin "8") (pinfunction "OUT6_8") (pintype "output"))
    )
    (net (code "48") (name "Net-(U5-SCLK)") (class "Default")
      (node (ref "U5") (pin "9") (pinfunction "SCLK_9") (pintype "bidirectional"))
      (node (ref "U6") (pin "16") (pinfunction "SCLKI_16") (pintype "bidirectional"))
    )
    (net (code "49") (name "Net-(U5-SD0)") (class "Default")
      (node (ref "U5") (pin "10") (pinfunction "SD0_10") (pintype "bidirectional"))
      (node (ref "U6") (pin "15") (pinfunction "SDI_15") (pintype "bidirectional"))
    )
    (net (code "50") (name "Net-(U6-OUT1)") (class "Default")
      (node (ref "D11") (pin "3") (pinfunction "-_3") (pintype "passive"))
      (node (ref "U6") (pin "1") (pinfunction "OUT1_1") (pintype "output"))
    )
    (net (code "51") (name "Net-(U6-OUT2)") (class "Default")
      (node (ref "D11") (pin "2") (pinfunction "-_2") (pintype "passive"))
      (node (ref "U6") (pin "2") (pinfunction "OUT2_2") (pintype "output"))
    )
    (net (code "52") (name "Net-(U6-OUT3)") (class "Default")
      (node (ref "D11") (pin "1") (pinfunction "-_1") (pintype "passive"))
      (node (ref "U6") (pin "3") (pinfunction "OUT3_3") (pintype "output"))
    )
    (net (code "53") (name "Net-(U6-OUT4)") (class "Default")
      (node (ref "D12") (pin "3") (pinfunction "-_3") (pintype "passive"))
      (node (ref "U6") (pin "6") (pinfunction "OUT4_6") (pintype "power_in"))
    )
    (net (code "54") (name "Net-(U6-OUT5)") (class "Default")
      (node (ref "D12") (pin "2") (pinfunction "-_2") (pintype "passive"))
      (node (ref "U6") (pin "7") (pinfunction "OUT5_7") (pintype "output"))
    )
    (net (code "55") (name "Net-(U6-OUT6)") (class "Default")
      (node (ref "D12") (pin "1") (pinfunction "-_1") (pintype "passive"))
      (node (ref "U6") (pin "8") (pinfunction "OUT6_8") (pintype "output"))
    )
    (net (code "56") (name "Net-(U6-SCLK)") (class "Default")
      (node (ref "U6") (pin "9") (pinfunction "SCLK_9") (pintype "bidirectional"))
      (node (ref "U7") (pin "16") (pinfunction "SCLKI_16") (pintype "bidirectional"))
    )
    (net (code "57") (name "Net-(U6-SD0)") (class "Default")
      (node (ref "U6") (pin "10") (pinfunction "SD0_10") (pintype "bidirectional"))
      (node (ref "U7") (pin "15") (pinfunction "SDI_15") (pintype "bidirectional"))
    )
    (net (code "58") (name "Net-(U7-OUT1)") (class "Default")
      (node (ref "D13") (pin "3") (pinfunction "-_3") (pintype "passive"))
      (node (ref "U7") (pin "1") (pinfunction "OUT1_1") (pintype "output"))
    )
    (net (code "59") (name "Net-(U7-OUT2)") (class "Default")
      (node (ref "D13") (pin "2") (pinfunction "-_2") (pintype "passive"))
      (node (ref "U7") (pin "2") (pinfunction "OUT2_2") (pintype "output"))
    )
    (net (code "60") (name "Net-(U7-OUT3)") (class "Default")
      (node (ref "D13") (pin "1") (pinfunction "-_1") (pintype "passive"))
      (node (ref "U7") (pin "3") (pinfunction "OUT3_3") (pintype "output"))
    )
    (net (code "61") (name "Net-(U7-OUT4)") (class "Default")
      (node (ref "D14") (pin "3") (pinfunction "-_3") (pintype "passive"))
      (node (ref "U7") (pin "6") (pinfunction "OUT4_6") (pintype "power_in"))
    )
    (net (code "62") (name "Net-(U7-OUT5)") (class "Default")
      (node (ref "D14") (pin "2") (pinfunction "-_2") (pintype "passive"))
      (node (ref "U7") (pin "7") (pinfunction "OUT5_7") (pintype "output"))
    )
    (net (code "63") (name "Net-(U7-OUT6)") (class "Default")
      (node (ref "D14") (pin "1") (pinfunction "-_1") (pintype "passive"))
      (node (ref "U7") (pin "8") (pinfunction "OUT6_8") (pintype "output"))
    )
    (net (code "64") (name "Net-(U7-SCLK)") (class "Default")
      (node (ref "U7") (pin "9") (pinfunction "SCLK_9") (pintype "bidirectional"))
      (node (ref "U8") (pin "16") (pinfunction "SCLKI_16") (pintype "bidirectional"))
    )
    (net (code "65") (name "Net-(U7-SD0)") (class "Default")
      (node (ref "U7") (pin "10") (pinfunction "SD0_10") (pintype "bidirectional"))
      (node (ref "U8") (pin "15") (pinfunction "SDI_15") (pintype "bidirectional"))
    )
    (net (code "66") (name "Net-(U8-OUT1)") (class "Default")
      (node (ref "D15") (pin "3") (pinfunction "-_3") (pintype "passive"))
      (node (ref "U8") (pin "1") (pinfunction "OUT1_1") (pintype "output"))
    )
    (net (code "67") (name "Net-(U8-OUT2)") (class "Default")
      (node (ref "D15") (pin "2") (pinfunction "-_2") (pintype "passive"))
      (node (ref "U8") (pin "2") (pinfunction "OUT2_2") (pintype "output"))
    )
    (net (code "68") (name "Net-(U8-OUT3)") (class "Default")
      (node (ref "D15") (pin "1") (pinfunction "-_1") (pintype "passive"))
      (node (ref "U8") (pin "3") (pinfunction "OUT3_3") (pintype "output"))
    )
    (net (code "69") (name "Net-(U8-OUT4)") (class "Default")
      (node (ref "D16") (pin "3") (pinfunction "-_3") (pintype "passive"))
      (node (ref "U8") (pin "6") (pinfunction "OUT4_6") (pintype "power_in"))
    )
    (net (code "70") (name "Net-(U8-OUT5)") (class "Default")
      (node (ref "D16") (pin "2") (pinfunction "-_2") (pintype "passive"))
      (node (ref "U8") (pin "7") (pinfunction "OUT5_7") (pintype "output"))
    )
    (net (code "71") (name "Net-(U8-OUT6)") (class "Default")
      (node (ref "D16") (pin "1") (pinfunction "-_1") (pintype "passive"))
      (node (ref "U8") (pin "8") (pinfunction "OUT6_8") (pintype "output"))
    )
    (net (code "72") (name "Net-(U8-SCLK)") (class "Default")
      (node (ref "U8") (pin "9") (pinfunction "SCLK_9") (pintype "bidirectional"))
      (node (ref "U9") (pin "16") (pinfunction "SCLKI_16") (pintype "bidirectional"))
    )
    (net (code "73") (name "Net-(U8-SD0)") (class "Default")
      (node (ref "U8") (pin "10") (pinfunction "SD0_10") (pintype "bidirectional"))
      (node (ref "U9") (pin "15") (pinfunction "SDI_15") (pintype "bidirectional"))
    )
    (net (code "74") (name "Net-(U9-OUT1)") (class "Default")
      (node (ref "D17") (pin "3") (pinfunction "-_3") (pintype "passive"))
      (node (ref "U9") (pin "1") (pinfunction "OUT1_1") (pintype "output"))
    )
    (net (code "75") (name "Net-(U9-OUT2)") (class "Default")
      (node (ref "D17") (pin "2") (pinfunction "-_2") (pintype "passive"))
      (node (ref "U9") (pin "2") (pinfunction "OUT2_2") (pintype "output"))
    )
    (net (code "76") (name "Net-(U9-OUT3)") (class "Default")
      (node (ref "D17") (pin "1") (pinfunction "-_1") (pintype "passive"))
      (node (ref "U9") (pin "3") (pinfunction "OUT3_3") (pintype "output"))
    )
    (net (code "77") (name "Net-(U9-OUT4)") (class "Default")
      (node (ref "D18") (pin "3") (pinfunction "-_3") (pintype "passive"))
      (node (ref "U9") (pin "6") (pinfunction "OUT4_6") (pintype "power_in"))
    )
    (net (code "78") (name "Net-(U9-OUT5)") (class "Default")
      (node (ref "D18") (pin "2") (pinfunction "-_2") (pintype "passive"))
      (node (ref "U9") (pin "7") (pinfunction "OUT5_7") (pintype "output"))
    )
    (net (code "79") (name "Net-(U9-OUT6)") (class "Default")
      (node (ref "D18") (pin "1") (pinfunction "-_1") (pintype "passive"))
      (node (ref "U9") (pin "8") (pinfunction "OUT6_8") (pintype "output"))
    )
    (net (code "80") (name "Net-(U10-OUT1)") (class "Default")
      (node (ref "D19") (pin "3") (pinfunction "-_3") (pintype "passive"))
      (node (ref "U10") (pin "1") (pinfunction "OUT1_1") (pintype "output"))
    )
    (net (code "81") (name "Net-(U10-OUT2)") (class "Default")
      (node (ref "D19") (pin "2") (pinfunction "-_2") (pintype "passive"))
      (node (ref "U10") (pin "2") (pinfunction "OUT2_2") (pintype "output"))
    )
    (net (code "82") (name "Net-(U10-OUT3)") (class "Default")
      (node (ref "D19") (pin "1") (pinfunction "-_1") (pintype "passive"))
      (node (ref "U10") (pin "3") (pinfunction "OUT3_3") (pintype "output"))
    )
    (net (code "83") (name "Net-(U10-OUT4)") (class "Default")
      (node (ref "D20") (pin "3") (pinfunction "-_3") (pintype "passive"))
      (node (ref "U10") (pin "6") (pinfunction "OUT4_6") (pintype "power_in"))
    )
    (net (code "84") (name "Net-(U10-OUT5)") (class "Default")
      (node (ref "D20") (pin "2") (pinfunction "-_2") (pintype "passive"))
      (node (ref "U10") (pin "7") (pinfunction "OUT5_7") (pintype "output"))
    )
    (net (code "85") (name "Net-(U10-OUT6)") (class "Default")
      (node (ref "D20") (pin "1") (pinfunction "-_1") (pintype "passive"))
      (node (ref "U10") (pin "8") (pinfunction "OUT6_8") (pintype "output"))
    )
    (net (code "86") (name "Net-(U10-SCLKI)") (class "Default")
      (node (ref "U10") (pin "16") (pinfunction "SCLKI_16") (pintype "bidirectional"))
      (node (ref "U9") (pin "9") (pinfunction "SCLK_9") (pintype "bidirectional"))
    )
    (net (code "87") (name "Net-(U10-SDI)") (class "Default")
      (node (ref "U10") (pin "15") (pinfunction "SDI_15") (pintype "bidirectional"))
      (node (ref "U9") (pin "10") (pinfunction "SD0_10") (pintype "bidirectional"))
    )
    (net (code "88") (name "Net-(U11-OUT1)") (class "Default")
      (node (ref "D21") (pin "3") (pinfunction "-_3") (pintype "passive"))
      (node (ref "U11") (pin "1") (pinfunction "OUT1_1") (pintype "output"))
    )
    (net (code "89") (name "Net-(U11-OUT2)") (class "Default")
      (node (ref "D21") (pin "2") (pinfunction "-_2") (pintype "passive"))
      (node (ref "U11") (pin "2") (pinfunction "OUT2_2") (pintype "output"))
    )
    (net (code "90") (name "Net-(U11-OUT3)") (class "Default")
      (node (ref "D21") (pin "1") (pinfunction "-_1") (pintype "passive"))
      (node (ref "U11") (pin "3") (pinfunction "OUT3_3") (pintype "output"))
    )
    (net (code "91") (name "Net-(U11-OUT4)") (class "Default")
      (node (ref "D22") (pin "3") (pinfunction "-_3") (pintype "passive"))
      (node (ref "U11") (pin "6") (pinfunction "OUT4_6") (pintype "power_in"))
    )
    (net (code "92") (name "Net-(U11-OUT5)") (class "Default")
      (node (ref "D22") (pin "2") (pinfunction "-_2") (pintype "passive"))
      (node (ref "U11") (pin "7") (pinfunction "OUT5_7") (pintype "output"))
    )
    (net (code "93") (name "Net-(U11-OUT6)") (class "Default")
      (node (ref "D22") (pin "1") (pinfunction "-_1") (pintype "passive"))
      (node (ref "U11") (pin "8") (pinfunction "OUT6_8") (pintype "output"))
    )
    (net (code "94") (name "Net-(U11-SCLK)") (class "Default")
      (node (ref "U11") (pin "9") (pinfunction "SCLK_9") (pintype "bidirectional"))
      (node (ref "U12") (pin "16") (pinfunction "SCLKI_16") (pintype "bidirectional"))
    )
    (net (code "95") (name "Net-(U11-SD0)") (class "Default")
      (node (ref "U11") (pin "10") (pinfunction "SD0_10") (pintype "bidirectional"))
      (node (ref "U12") (pin "15") (pinfunction "SDI_15") (pintype "bidirectional"))
    )
    (net (code "96") (name "Net-(U12-OUT1)") (class "Default")
      (node (ref "D23") (pin "3") (pinfunction "-_3") (pintype "passive"))
      (node (ref "U12") (pin "1") (pinfunction "OUT1_1") (pintype "output"))
    )
    (net (code "97") (name "Net-(U12-OUT2)") (class "Default")
      (node (ref "D23") (pin "2") (pinfunction "-_2") (pintype "passive"))
      (node (ref "U12") (pin "2") (pinfunction "OUT2_2") (pintype "output"))
    )
    (net (code "98") (name "Net-(U12-OUT3)") (class "Default")
      (node (ref "D23") (pin "1") (pinfunction "-_1") (pintype "passive"))
      (node (ref "U12") (pin "3") (pinfunction "OUT3_3") (pintype "output"))
    )
    (net (code "99") (name "Net-(U12-OUT4)") (class "Default")
      (node (ref "D24") (pin "3") (pinfunction "-_3") (pintype "passive"))
      (node (ref "U12") (pin "6") (pinfunction "OUT4_6") (pintype "power_in"))
    )
    (net (code "100") (name "Net-(U12-OUT5)") (class "Default")
      (node (ref "D24") (pin "2") (pinfunction "-_2") (pintype "passive"))
      (node (ref "U12") (pin "7") (pinfunction "OUT5_7") (pintype "output"))
    )
    (net (code "101") (name "Net-(U12-OUT6)") (class "Default")
      (node (ref "D24") (pin "1") (pinfunction "-_1") (pintype "passive"))
      (node (ref "U12") (pin "8") (pinfunction "OUT6_8") (pintype "output"))
    )
    (net (code "102") (name "Net-(U12-SCLK)") (class "Default")
      (node (ref "U12") (pin "9") (pinfunction "SCLK_9") (pintype "bidirectional"))
      (node (ref "U13") (pin "16") (pinfunction "SCLKI_16") (pintype "bidirectional"))
    )
    (net (code "103") (name "Net-(U12-SD0)") (class "Default")
      (node (ref "U12") (pin "10") (pinfunction "SD0_10") (pintype "bidirectional"))
      (node (ref "U13") (pin "15") (pinfunction "SDI_15") (pintype "bidirectional"))
    )
    (net (code "104") (name "Net-(U13-OUT1)") (class "Default")
      (node (ref "D25") (pin "3") (pinfunction "-_3") (pintype "passive"))
      (node (ref "U13") (pin "1") (pinfunction "OUT1_1") (pintype "output"))
    )
    (net (code "105") (name "Net-(U13-OUT2)") (class "Default")
      (node (ref "D25") (pin "2") (pinfunction "-_2") (pintype "passive"))
      (node (ref "U13") (pin "2") (pinfunction "OUT2_2") (pintype "output"))
    )
    (net (code "106") (name "Net-(U13-OUT3)") (class "Default")
      (node (ref "D25") (pin "1") (pinfunction "-_1") (pintype "passive"))
      (node (ref "U13") (pin "3") (pinfunction "OUT3_3") (pintype "output"))
    )
    (net (code "107") (name "Net-(U13-OUT4)") (class "Default")
      (node (ref "D26") (pin "3") (pinfunction "-_3") (pintype "passive"))
      (node (ref "U13") (pin "6") (pinfunction "OUT4_6") (pintype "power_in"))
    )
    (net (code "108") (name "Net-(U13-OUT5)") (class "Default")
      (node (ref "D26") (pin "2") (pinfunction "-_2") (pintype "passive"))
      (node (ref "U13") (pin "7") (pinfunction "OUT5_7") (pintype "output"))
    )
    (net (code "109") (name "Net-(U13-OUT6)") (class "Default")
      (node (ref "D26") (pin "1") (pinfunction "-_1") (pintype "passive"))
      (node (ref "U13") (pin "8") (pinfunction "OUT6_8") (pintype "output"))
    )
    (net (code "110") (name "Net-(U13-SCLK)") (class "Default")
      (node (ref "U13") (pin "9") (pinfunction "SCLK_9") (pintype "bidirectional"))
      (node (ref "U14") (pin "16") (pinfunction "SCLKI_16") (pintype "bidirectional"))
    )
    (net (code "111") (name "Net-(U13-SD0)") (class "Default")
      (node (ref "U13") (pin "10") (pinfunction "SD0_10") (pintype "bidirectional"))
      (node (ref "U14") (pin "15") (pinfunction "SDI_15") (pintype "bidirectional"))
    )
    (net (code "112") (name "Net-(U14-OUT1)") (class "Default")
      (node (ref "D27") (pin "3") (pinfunction "-_3") (pintype "passive"))
      (node (ref "U14") (pin "1") (pinfunction "OUT1_1") (pintype "output"))
    )
    (net (code "113") (name "Net-(U14-OUT2)") (class "Default")
      (node (ref "D27") (pin "2") (pinfunction "-_2") (pintype "passive"))
      (node (ref "U14") (pin "2") (pinfunction "OUT2_2") (pintype "output"))
    )
    (net (code "114") (name "Net-(U14-OUT3)") (class "Default")
      (node (ref "D27") (pin "1") (pinfunction "-_1") (pintype "passive"))
      (node (ref "U14") (pin "3") (pinfunction "OUT3_3") (pintype "output"))
    )
    (net (code "115") (name "Net-(U14-OUT4)") (class "Default")
      (node (ref "D28") (pin "3") (pinfunction "-_3") (pintype "passive"))
      (node (ref "U14") (pin "6") (pinfunction "OUT4_6") (pintype "power_in"))
    )
    (net (code "116") (name "Net-(U14-OUT5)") (class "Default")
      (node (ref "D28") (pin "2") (pinfunction "-_2") (pintype "passive"))
      (node (ref "U14") (pin "7") (pinfunction "OUT5_7") (pintype "output"))
    )
    (net (code "117") (name "Net-(U14-OUT6)") (class "Default")
      (node (ref "D28") (pin "1") (pinfunction "-_1") (pintype "passive"))
      (node (ref "U14") (pin "8") (pinfunction "OUT6_8") (pintype "output"))
    )
    (net (code "118") (name "Net-(U14-SCLK)") (class "Default")
      (node (ref "U14") (pin "9") (pinfunction "SCLK_9") (pintype "bidirectional"))
      (node (ref "U15") (pin "16") (pinfunction "SCLKI_16") (pintype "bidirectional"))
    )
    (net (code "119") (name "Net-(U14-SD0)") (class "Default")
      (node (ref "U14") (pin "10") (pinfunction "SD0_10") (pintype "bidirectional"))
      (node (ref "U15") (pin "15") (pinfunction "SDI_15") (pintype "bidirectional"))
    )
    (net (code "120") (name "Net-(U15-OUT1)") (class "Default")
      (node (ref "D29") (pin "3") (pinfunction "-_3") (pintype "passive"))
      (node (ref "U15") (pin "1") (pinfunction "OUT1_1") (pintype "output"))
    )
    (net (code "121") (name "Net-(U15-OUT2)") (class "Default")
      (node (ref "D29") (pin "2") (pinfunction "-_2") (pintype "passive"))
      (node (ref "U15") (pin "2") (pinfunction "OUT2_2") (pintype "output"))
    )
    (net (code "122") (name "Net-(U15-OUT3)") (class "Default")
      (node (ref "D29") (pin "1") (pinfunction "-_1") (pintype "passive"))
      (node (ref "U15") (pin "3") (pinfunction "OUT3_3") (pintype "output"))
    )
    (net (code "123") (name "Net-(U15-OUT4)") (class "Default")
      (node (ref "D30") (pin "3") (pinfunction "-_3") (pintype "passive"))
      (node (ref "U15") (pin "6") (pinfunction "OUT4_6") (pintype "power_in"))
    )
    (net (code "124") (name "Net-(U15-OUT5)") (class "Default")
      (node (ref "D30") (pin "2") (pinfunction "-_2") (pintype "passive"))
      (node (ref "U15") (pin "7") (pinfunction "OUT5_7") (pintype "output"))
    )
    (net (code "125") (name "Net-(U15-OUT6)") (class "Default")
      (node (ref "D30") (pin "1") (pinfunction "-_1") (pintype "passive"))
      (node (ref "U15") (pin "8") (pinfunction "OUT6_8") (pintype "output"))
    )
    (net (code "126") (name "unconnected-(U1-NC-Pad12)") (class "Default")
      (node (ref "U1") (pin "12") (pinfunction "NC_12") (pintype "passive+no_connect"))
    )
    (net (code "127") (name "unconnected-(U1-OMODE-Pad11)") (class "Default")
      (node (ref "U1") (pin "11") (pinfunction "OMODE_11") (pintype "bidirectional+no_connect"))
    )
    (net (code "128") (name "unconnected-(U1-PMODE-Pad14)") (class "Default")
      (node (ref "U1") (pin "14") (pinfunction "PMODE_14") (pintype "bidirectional+no_connect"))
    )
    (net (code "129") (name "unconnected-(U2-NC-Pad12)") (class "Default")
      (node (ref "U2") (pin "12") (pinfunction "NC_12") (pintype "passive+no_connect"))
    )
    (net (code "130") (name "unconnected-(U2-OMODE-Pad11)") (class "Default")
      (node (ref "U2") (pin "11") (pinfunction "OMODE_11") (pintype "bidirectional+no_connect"))
    )
    (net (code "131") (name "unconnected-(U2-PMODE-Pad14)") (class "Default")
      (node (ref "U2") (pin "14") (pinfunction "PMODE_14") (pintype "bidirectional+no_connect"))
    )
    (net (code "132") (name "unconnected-(U3-NC-Pad12)") (class "Default")
      (node (ref "U3") (pin "12") (pinfunction "NC_12") (pintype "passive+no_connect"))
    )
    (net (code "133") (name "unconnected-(U3-OMODE-Pad11)") (class "Default")
      (node (ref "U3") (pin "11") (pinfunction "OMODE_11") (pintype "bidirectional+no_connect"))
    )
    (net (code "134") (name "unconnected-(U3-PMODE-Pad14)") (class "Default")
      (node (ref "U3") (pin "14") (pinfunction "PMODE_14") (pintype "bidirectional+no_connect"))
    )
    (net (code "135") (name "unconnected-(U4-NC-Pad12)") (class "Default")
      (node (ref "U4") (pin "12") (pinfunction "NC_12") (pintype "passive+no_connect"))
    )
    (net (code "136") (name "unconnected-(U4-OMODE-Pad11)") (class "Default")
      (node (ref "U4") (pin "11") (pinfunction "OMODE_11") (pintype "bidirectional+no_connect"))
    )
    (net (code "137") (name "unconnected-(U4-PMODE-Pad14)") (class "Default")
      (node (ref "U4") (pin "14") (pinfunction "PMODE_14") (pintype "bidirectional+no_connect"))
    )
    (net (code "138") (name "unconnected-(U5-NC-Pad12)") (class "Default")
      (node (ref "U5") (pin "12") (pinfunction "NC_12") (pintype "passive+no_connect"))
    )
    (net (code "139") (name "unconnected-(U5-OMODE-Pad11)") (class "Default")
      (node (ref "U5") (pin "11") (pinfunction "OMODE_11") (pintype "bidirectional+no_connect"))
    )
    (net (code "140") (name "unconnected-(U5-PMODE-Pad14)") (class "Default")
      (node (ref "U5") (pin "14") (pinfunction "PMODE_14") (pintype "bidirectional+no_connect"))
    )
    (net (code "141") (name "unconnected-(U6-NC-Pad12)") (class "Default")
      (node (ref "U6") (pin "12") (pinfunction "NC_12") (pintype "passive+no_connect"))
    )
    (net (code "142") (name "unconnected-(U6-OMODE-Pad11)") (class "Default")
      (node (ref "U6") (pin "11") (pinfunction "OMODE_11") (pintype "bidirectional+no_connect"))
    )
    (net (code "143") (name "unconnected-(U6-PMODE-Pad14)") (class "Default")
      (node (ref "U6") (pin "14") (pinfunction "PMODE_14") (pintype "bidirectional+no_connect"))
    )
    (net (code "144") (name "unconnected-(U7-NC-Pad12)") (class "Default")
      (node (ref "U7") (pin "12") (pinfunction "NC_12") (pintype "passive+no_connect"))
    )
    (net (code "145") (name "unconnected-(U7-OMODE-Pad11)") (class "Default")
      (node (ref "U7") (pin "11") (pinfunction "OMODE_11") (pintype "bidirectional+no_connect"))
    )
    (net (code "146") (name "unconnected-(U7-PMODE-Pad14)") (class "Default")
      (node (ref "U7") (pin "14") (pinfunction "PMODE_14") (pintype "bidirectional+no_connect"))
    )
    (net (code "147") (name "unconnected-(U8-NC-Pad12)") (class "Default")
      (node (ref "U8") (pin "12") (pinfunction "NC_12") (pintype "passive+no_connect"))
    )
    (net (code "148") (name "unconnected-(U8-OMODE-Pad11)") (class "Default")
      (node (ref "U8") (pin "11") (pinfunction "OMODE_11") (pintype "bidirectional+no_connect"))
    )
    (net (code "149") (name "unconnected-(U8-PMODE-Pad14)") (class "Default")
      (node (ref "U8") (pin "14") (pinfunction "PMODE_14") (pintype "bidirectional+no_connect"))
    )
    (net (code "150") (name "unconnected-(U9-NC-Pad12)") (class "Default")
      (node (ref "U9") (pin "12") (pinfunction "NC_12") (pintype "passive+no_connect"))
    )
    (net (code "151") (name "unconnected-(U9-OMODE-Pad11)") (class "Default")
      (node (ref "U9") (pin "11") (pinfunction "OMODE_11") (pintype "bidirectional+no_connect"))
    )
    (net (code "152") (name "unconnected-(U9-PMODE-Pad14)") (class "Default")
      (node (ref "U9") (pin "14") (pinfunction "PMODE_14") (pintype "bidirectional+no_connect"))
    )
    (net (code "153") (name "unconnected-(U10-NC-Pad12)") (class "Default")
      (node (ref "U10") (pin "12") (pinfunction "NC_12") (pintype "passive+no_connect"))
    )
    (net (code "154") (name "unconnected-(U10-OMODE-Pad11)") (class "Default")
      (node (ref "U10") (pin "11") (pinfunction "OMODE_11") (pintype "bidirectional+no_connect"))
    )
    (net (code "155") (name "unconnected-(U10-PMODE-Pad14)") (class "Default")
      (node (ref "U10") (pin "14") (pinfunction "PMODE_14") (pintype "bidirectional+no_connect"))
    )
    (net (code "156") (name "unconnected-(U11-NC-Pad12)") (class "Default")
      (node (ref "U11") (pin "12") (pinfunction "NC_12") (pintype "passive+no_connect"))
    )
    (net (code "157") (name "unconnected-(U11-OMODE-Pad11)") (class "Default")
      (node (ref "U11") (pin "11") (pinfunction "OMODE_11") (pintype "bidirectional+no_connect"))
    )
    (net (code "158") (name "unconnected-(U11-PMODE-Pad14)") (class "Default")
      (node (ref "U11") (pin "14") (pinfunction "PMODE_14") (pintype "bidirectional+no_connect"))
    )
    (net (code "159") (name "unconnected-(U12-NC-Pad12)") (class "Default")
      (node (ref "U12") (pin "12") (pinfunction "NC_12") (pintype "passive+no_connect"))
    )
    (net (code "160") (name "unconnected-(U12-OMODE-Pad11)") (class "Default")
      (node (ref "U12") (pin "11") (pinfunction "OMODE_11") (pintype "bidirectional+no_connect"))
    )
    (net (code "161") (name "unconnected-(U12-PMODE-Pad14)") (class "Default")
      (node (ref "U12") (pin "14") (pinfunction "PMODE_14") (pintype "bidirectional+no_connect"))
    )
    (net (code "162") (name "unconnected-(U13-NC-Pad12)") (class "Default")
      (node (ref "U13") (pin "12") (pinfunction "NC_12") (pintype "passive+no_connect"))
    )
    (net (code "163") (name "unconnected-(U13-OMODE-Pad11)") (class "Default")
      (node (ref "U13") (pin "11") (pinfunction "OMODE_11") (pintype "bidirectional+no_connect"))
    )
    (net (code "164") (name "unconnected-(U13-PMODE-Pad14)") (class "Default")
      (node (ref "U13") (pin "14") (pinfunction "PMODE_14") (pintype "bidirectional+no_connect"))
    )
    (net (code "165") (name "unconnected-(U14-NC-Pad12)") (class "Default")
      (node (ref "U14") (pin "12") (pinfunction "NC_12") (pintype "passive+no_connect"))
    )
    (net (code "166") (name "unconnected-(U14-OMODE-Pad11)") (class "Default")
      (node (ref "U14") (pin "11") (pinfunction "OMODE_11") (pintype "bidirectional+no_connect"))
    )
    (net (code "167") (name "unconnected-(U14-PMODE-Pad14)") (class "Default")
      (node (ref "U14") (pin "14") (pinfunction "PMODE_14") (pintype "bidirectional+no_connect"))
    )
    (net (code "168") (name "unconnected-(U15-NC-Pad12)") (class "Default")
      (node (ref "U15") (pin "12") (pinfunction "NC_12") (pintype "passive+no_connect"))
    )
    (net (code "169") (name "unconnected-(U15-OMODE-Pad11)") (class "Default")
      (node (ref "U15") (pin "11") (pinfunction "OMODE_11") (pintype "bidirectional+no_connect"))
    )
    (net (code "170") (name "unconnected-(U15-PMODE-Pad14)") (class "Default")
      (node (ref "U15") (pin "14") (pinfunction "PMODE_14") (pintype "bidirectional+no_connect"))
    )
  )
)
